# IGNITERS.net
KiCad netlist of a schematic drawn in Altium Designer
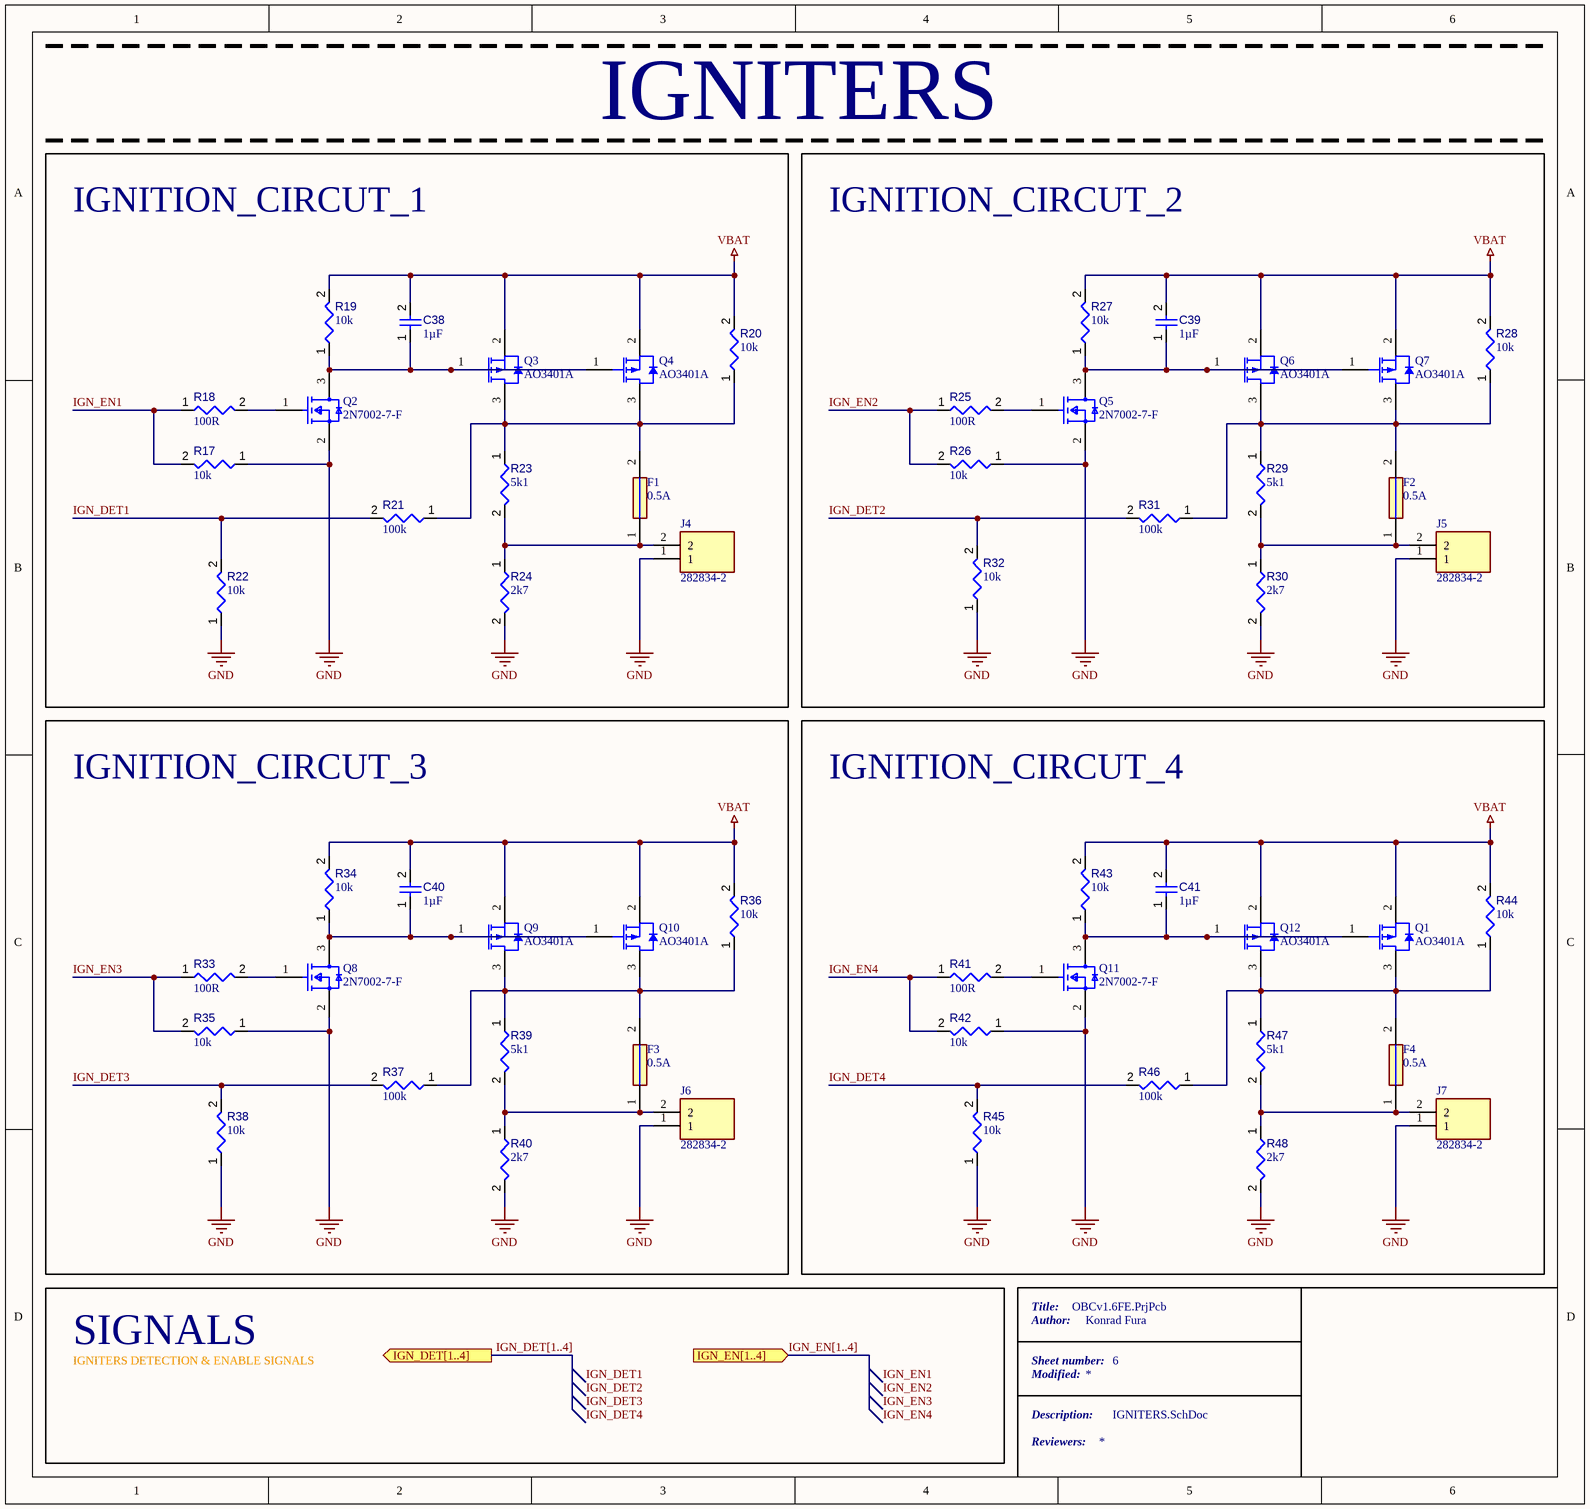
[diagram p0: IGNITERS.SchDoc]

(export (version "E")
  (design (tool "Eeschema 10.0.6"))
  (components
    (comp (ref "C38")
      (value "1µF")
      (footprint "CAPC0402(1005)60_L")
      (description "Chip Capacitor, 1µF +/-20%, 10V, 0402, Thickness 0.6 mm")
      (fields (field (name "TOLERANCE") "10%") (field (name "Comment") "Capacitor 1µF +/-20% 10V 0402"))
      (libsource (lib "PWr in Space team") (part "CAP-NP-2"))
    )
    (comp (ref "C39")
      (value "1µF")
      (footprint "CAPC0402(1005)60_L")
      (description "Chip Capacitor, 1µF +/-20%, 10V, 0402, Thickness 0.6 mm")
      (fields (field (name "TOLERANCE") "10%") (field (name "Comment") "Capacitor 1µF +/-20% 10V 0402"))
      (libsource (lib "PWr in Space team") (part "CAP-NP-2"))
    )
    (comp (ref "C40")
      (value "1µF")
      (footprint "CAPC0402(1005)60_L")
      (description "Chip Capacitor, 1µF +/-20%, 10V, 0402, Thickness 0.6 mm")
      (fields (field (name "TOLERANCE") "10%") (field (name "Comment") "Capacitor 1µF +/-20% 10V 0402"))
      (libsource (lib "PWr in Space team") (part "CAP-NP-2"))
    )
    (comp (ref "C41")
      (value "1µF")
      (footprint "CAPC0402(1005)60_L")
      (description "Chip Capacitor, 1µF +/-20%, 10V, 0402, Thickness 0.6 mm")
      (fields (field (name "TOLERANCE") "10%") (field (name "Comment") "Capacitor 1µF +/-20% 10V 0402"))
      (libsource (lib "PWr in Space team") (part "CAP-NP-2"))
    )
    (comp (ref "F1")
      (value "0.5A")
      (footprint "SamacSys:FUSC2114X75N")
      (description "Fuse")
      (fields
        (field (name "MANUFACTURER_PART_NUMBER") "0805L020/24YR")
        (field (name "MOUSER PART NUMBER") "576-0805L020/24YR")
      )
      (libsource (lib "*") (part "0805L020_24YR"))
    )
    (comp (ref "F2")
      (value "0.5A")
      (footprint "SamacSys:FUSC2114X75N")
      (description "Fuse")
      (fields
        (field (name "MANUFACTURER_PART_NUMBER") "0805L020/24YR")
        (field (name "MOUSER PART NUMBER") "576-0805L020/24YR")
      )
      (libsource (lib "*") (part "0805L020_24YR"))
    )
    (comp (ref "F3")
      (value "0.5A")
      (footprint "SamacSys:FUSC2114X75N")
      (description "Fuse")
      (fields
        (field (name "MANUFACTURER_PART_NUMBER") "0805L020/24YR")
        (field (name "MOUSER PART NUMBER") "576-0805L020/24YR")
      )
      (libsource (lib "*") (part "0805L020_24YR"))
    )
    (comp (ref "F4")
      (value "0.5A")
      (footprint "SamacSys:FUSC2114X75N")
      (description "Fuse")
      (fields
        (field (name "MANUFACTURER_PART_NUMBER") "0805L020/24YR")
        (field (name "MOUSER PART NUMBER") "576-0805L020/24YR")
      )
      (libsource (lib "*") (part "0805L020_24YR"))
    )
    (comp (ref "J4")
      (value "282834-2")
      (footprint "SamacSys:282834-2_1")
      (description "Connector")
      (fields (field (name "MOUSER PART NUMBER") "571-282834-2"))
      (libsource (lib "*") (part "282834-2"))
    )
    (comp (ref "J5")
      (value "282834-2")
      (footprint "SamacSys:282834-2_1")
      (description "Connector")
      (fields (field (name "MOUSER PART NUMBER") "571-282834-2"))
      (libsource (lib "*") (part "282834-2"))
    )
    (comp (ref "J6")
      (value "282834-2")
      (footprint "SamacSys:282834-2_1")
      (description "Connector")
      (fields (field (name "MOUSER PART NUMBER") "571-282834-2"))
      (libsource (lib "*") (part "282834-2"))
    )
    (comp (ref "J7")
      (value "282834-2")
      (footprint "SamacSys:282834-2_1")
      (description "Connector")
      (fields (field (name "MOUSER PART NUMBER") "571-282834-2"))
      (libsource (lib "*") (part "282834-2"))
    )
    (comp (ref "Q1")
      (value "AO3401A")
      (footprint "AO-SOT-23-3L_V")
      (description "P-Channel MOSFET, 30 V, 4 A, -55 to 150 degC, 3-Pin SOT-23-3L, RoHS, Tape and Reel")
      (fields (field (name "MANUFACTURER") "Alpha and Omega"))
      (libsource (lib "Altium Content Vault") (part "PEMOS-GSD-3"))
    )
    (comp (ref "Q2")
      (value "2N7002-7-F")
      (footprint "FP-SOT23-MFG")
      (description "MOSFET N-CH 60V 115MA SOT23-3")
      (fields (field (name "VOLTAGE") "60V"))
      (libsource (lib "Altium Content Vault") (part "3b9c635fedb024a5347a57b145af9cc"))
    )
    (comp (ref "Q3")
      (value "AO3401A")
      (footprint "AO-SOT-23-3L_V")
      (description "P-Channel MOSFET, 30 V, 4 A, -55 to 150 degC, 3-Pin SOT-23-3L, RoHS, Tape and Reel")
      (fields (field (name "MANUFACTURER") "Alpha and Omega"))
      (libsource (lib "Altium Content Vault") (part "PEMOS-GSD-3"))
    )
    (comp (ref "Q4")
      (value "AO3401A")
      (footprint "AO-SOT-23-3L_V")
      (description "P-Channel MOSFET, 30 V, 4 A, -55 to 150 degC, 3-Pin SOT-23-3L, RoHS, Tape and Reel")
      (fields (field (name "MANUFACTURER") "Alpha and Omega"))
      (libsource (lib "Altium Content Vault") (part "PEMOS-GSD-3"))
    )
    (comp (ref "Q5")
      (value "2N7002-7-F")
      (footprint "FP-SOT23-MFG")
      (description "MOSFET N-CH 60V 115MA SOT23-3")
      (fields (field (name "VOLTAGE") "60V"))
      (libsource (lib "Altium Content Vault") (part "3b9c635fedb024a5347a57b145af9cc"))
    )
    (comp (ref "Q6")
      (value "AO3401A")
      (footprint "AO-SOT-23-3L_V")
      (description "P-Channel MOSFET, 30 V, 4 A, -55 to 150 degC, 3-Pin SOT-23-3L, RoHS, Tape and Reel")
      (fields (field (name "MANUFACTURER") "Alpha and Omega"))
      (libsource (lib "Altium Content Vault") (part "PEMOS-GSD-3"))
    )
    (comp (ref "Q7")
      (value "AO3401A")
      (footprint "AO-SOT-23-3L_V")
      (description "P-Channel MOSFET, 30 V, 4 A, -55 to 150 degC, 3-Pin SOT-23-3L, RoHS, Tape and Reel")
      (fields (field (name "MANUFACTURER") "Alpha and Omega"))
      (libsource (lib "Altium Content Vault") (part "PEMOS-GSD-3"))
    )
    (comp (ref "Q8")
      (value "2N7002-7-F")
      (footprint "FP-SOT23-MFG")
      (description "MOSFET N-CH 60V 115MA SOT23-3")
      (fields (field (name "VOLTAGE") "60V"))
      (libsource (lib "Altium Content Vault") (part "3b9c635fedb024a5347a57b145af9cc"))
    )
    (comp (ref "Q9")
      (value "AO3401A")
      (footprint "AO-SOT-23-3L_V")
      (description "P-Channel MOSFET, 30 V, 4 A, -55 to 150 degC, 3-Pin SOT-23-3L, RoHS, Tape and Reel")
      (fields (field (name "MANUFACTURER") "Alpha and Omega"))
      (libsource (lib "Altium Content Vault") (part "PEMOS-GSD-3"))
    )
    (comp (ref "Q10")
      (value "AO3401A")
      (footprint "AO-SOT-23-3L_V")
      (description "P-Channel MOSFET, 30 V, 4 A, -55 to 150 degC, 3-Pin SOT-23-3L, RoHS, Tape and Reel")
      (fields (field (name "MANUFACTURER") "Alpha and Omega"))
      (libsource (lib "Altium Content Vault") (part "PEMOS-GSD-3"))
    )
    (comp (ref "Q11")
      (value "2N7002-7-F")
      (footprint "FP-SOT23-MFG")
      (description "MOSFET N-CH 60V 115MA SOT23-3")
      (fields (field (name "VOLTAGE") "60V"))
      (libsource (lib "Altium Content Vault") (part "3b9c635fedb024a5347a57b145af9cc"))
    )
    (comp (ref "Q12")
      (value "AO3401A")
      (footprint "AO-SOT-23-3L_V")
      (description "P-Channel MOSFET, 30 V, 4 A, -55 to 150 degC, 3-Pin SOT-23-3L, RoHS, Tape and Reel")
      (fields (field (name "MANUFACTURER") "Alpha and Omega"))
      (libsource (lib "Altium Content Vault") (part "PEMOS-GSD-3"))
    )
    (comp (ref "R17")
      (value "10k")
      (footprint "RESC0402(1005)_L")
      (description "Chip Resistor, 10 kOhms, +/-1 %, 63 mW, -55 to 125 degC, 0402")
      (fields (field (name "POWER") "63mW") (field (name "TOLERANCE") "1%"))
      (libsource (lib "PWr in Space team") (part "RES-2"))
    )
    (comp (ref "R18")
      (value "100R")
      (footprint "RESC0402(1005)_L")
      (description "Chip Resistor, 100 Ohms, +/-1 %, 63 mW, -55 to 155 degC, 0402")
      (fields (field (name "POWER") "63mW") (field (name "TOLERANCE") "1%"))
      (libsource (lib "PWr in Space team") (part "RES-2"))
    )
    (comp (ref "R19")
      (value "10k")
      (footprint "RESC0402(1005)_L")
      (description "Chip Resistor, 10 kOhms, +/-1 %, 63 mW, -55 to 125 degC, 0402")
      (fields (field (name "POWER") "63mW") (field (name "TOLERANCE") "1%"))
      (libsource (lib "PWr in Space team") (part "RES-2"))
    )
    (comp (ref "R20")
      (value "10k")
      (footprint "RESC0402(1005)_L")
      (description "Chip Resistor, 10 kOhms, +/-1 %, 63 mW, -55 to 125 degC, 0402")
      (fields (field (name "POWER") "63mW") (field (name "TOLERANCE") "1%"))
      (libsource (lib "PWr in Space team") (part "RES-2"))
    )
    (comp (ref "R21")
      (value "100k")
      (footprint "RESC0402(1005)_L")
      (description "Chip Resistor, 100 kOhms, +/-1 %, 63 mW, -55 to 155 degC, 0402")
      (fields (field (name "TOLERANCE") "1%") (field (name "POWER") "63mW"))
      (libsource (lib "PWr in Space team") (part "RES-2"))
    )
    (comp (ref "R22")
      (value "10k")
      (footprint "RESC0402(1005)_L")
      (description "Chip Resistor, 10 kOhms, +/-1 %, 63 mW, -55 to 125 degC, 0402")
      (fields (field (name "POWER") "63mW") (field (name "TOLERANCE") "1%"))
      (libsource (lib "PWr in Space team") (part "RES-2"))
    )
    (comp (ref "R23")
      (value "5k1")
      (footprint "RESC0402(1005)_L")
      (description "Chip Resistor, 5.1 kOhms, +/-1 %, 63 mW, -55 to 155 degC, 0402")
      (fields (field (name "TOLERANCE") "1%") (field (name "POWER") "63mW"))
      (libsource (lib "PWr in Space team") (part "RES-2"))
    )
    (comp (ref "R24")
      (value "2k7")
      (footprint "RESC0402(1005)_L")
      (description "Chip Resistor, 2.7 kOhms, +/-1 %, 63 mW, -55 to 155 degC, 0402")
      (fields (field (name "TOLERANCE") "1%") (field (name "POWER") "63mW"))
      (libsource (lib "PWr in Space team") (part "RES-2"))
    )
    (comp (ref "R25")
      (value "100R")
      (footprint "RESC0402(1005)_L")
      (description "Chip Resistor, 100 Ohms, +/-1 %, 63 mW, -55 to 155 degC, 0402")
      (fields (field (name "POWER") "63mW") (field (name "TOLERANCE") "1%"))
      (libsource (lib "PWr in Space team") (part "RES-2"))
    )
    (comp (ref "R26")
      (value "10k")
      (footprint "RESC0402(1005)_L")
      (description "Chip Resistor, 10 kOhms, +/-1 %, 63 mW, -55 to 125 degC, 0402")
      (fields (field (name "POWER") "63mW") (field (name "TOLERANCE") "1%"))
      (libsource (lib "PWr in Space team") (part "RES-2"))
    )
    (comp (ref "R27")
      (value "10k")
      (footprint "RESC0402(1005)_L")
      (description "Chip Resistor, 10 kOhms, +/-1 %, 63 mW, -55 to 125 degC, 0402")
      (fields (field (name "POWER") "63mW") (field (name "TOLERANCE") "1%"))
      (libsource (lib "PWr in Space team") (part "RES-2"))
    )
    (comp (ref "R28")
      (value "10k")
      (footprint "RESC0402(1005)_L")
      (description "Chip Resistor, 10 kOhms, +/-1 %, 63 mW, -55 to 125 degC, 0402")
      (fields (field (name "POWER") "63mW") (field (name "TOLERANCE") "1%"))
      (libsource (lib "PWr in Space team") (part "RES-2"))
    )
    (comp (ref "R29")
      (value "5k1")
      (footprint "RESC0402(1005)_L")
      (description "Chip Resistor, 5.1 kOhms, +/-1 %, 63 mW, -55 to 155 degC, 0402")
      (fields (field (name "TOLERANCE") "1%") (field (name "POWER") "63mW"))
      (libsource (lib "PWr in Space team") (part "RES-2"))
    )
    (comp (ref "R30")
      (value "2k7")
      (footprint "RESC0402(1005)_L")
      (description "Chip Resistor, 2.7 kOhms, +/-1 %, 63 mW, -55 to 155 degC, 0402")
      (fields (field (name "TOLERANCE") "1%") (field (name "POWER") "63mW"))
      (libsource (lib "PWr in Space team") (part "RES-2"))
    )
    (comp (ref "R31")
      (value "100k")
      (footprint "RESC0402(1005)_L")
      (description "Chip Resistor, 100 kOhms, +/-1 %, 63 mW, -55 to 155 degC, 0402")
      (fields (field (name "TOLERANCE") "1%") (field (name "POWER") "63mW"))
      (libsource (lib "PWr in Space team") (part "RES-2"))
    )
    (comp (ref "R32")
      (value "10k")
      (footprint "RESC0402(1005)_L")
      (description "Chip Resistor, 10 kOhms, +/-1 %, 63 mW, -55 to 125 degC, 0402")
      (fields (field (name "POWER") "63mW") (field (name "TOLERANCE") "1%"))
      (libsource (lib "PWr in Space team") (part "RES-2"))
    )
    (comp (ref "R33")
      (value "100R")
      (footprint "RESC0402(1005)_L")
      (description "Chip Resistor, 100 Ohms, +/-1 %, 63 mW, -55 to 155 degC, 0402")
      (fields (field (name "POWER") "63mW") (field (name "TOLERANCE") "1%"))
      (libsource (lib "PWr in Space team") (part "RES-2"))
    )
    (comp (ref "R34")
      (value "10k")
      (footprint "RESC0402(1005)_L")
      (description "Chip Resistor, 10 kOhms, +/-1 %, 63 mW, -55 to 125 degC, 0402")
      (fields (field (name "POWER") "63mW") (field (name "TOLERANCE") "1%"))
      (libsource (lib "PWr in Space team") (part "RES-2"))
    )
    (comp (ref "R35")
      (value "10k")
      (footprint "RESC0402(1005)_L")
      (description "Chip Resistor, 10 kOhms, +/-1 %, 63 mW, -55 to 125 degC, 0402")
      (fields (field (name "POWER") "63mW") (field (name "TOLERANCE") "1%"))
      (libsource (lib "PWr in Space team") (part "RES-2"))
    )
    (comp (ref "R36")
      (value "10k")
      (footprint "RESC0402(1005)_L")
      (description "Chip Resistor, 10 kOhms, +/-1 %, 63 mW, -55 to 125 degC, 0402")
      (fields (field (name "POWER") "63mW") (field (name "TOLERANCE") "1%"))
      (libsource (lib "PWr in Space team") (part "RES-2"))
    )
    (comp (ref "R37")
      (value "100k")
      (footprint "RESC0402(1005)_L")
      (description "Chip Resistor, 100 kOhms, +/-1 %, 63 mW, -55 to 155 degC, 0402")
      (fields (field (name "TOLERANCE") "1%") (field (name "POWER") "63mW"))
      (libsource (lib "PWr in Space team") (part "RES-2"))
    )
    (comp (ref "R38")
      (value "10k")
      (footprint "RESC0402(1005)_L")
      (description "Chip Resistor, 10 kOhms, +/-1 %, 63 mW, -55 to 125 degC, 0402")
      (fields (field (name "POWER") "63mW") (field (name "TOLERANCE") "1%"))
      (libsource (lib "PWr in Space team") (part "RES-2"))
    )
    (comp (ref "R39")
      (value "5k1")
      (footprint "RESC0402(1005)_L")
      (description "Chip Resistor, 5.1 kOhms, +/-1 %, 63 mW, -55 to 155 degC, 0402")
      (fields (field (name "TOLERANCE") "1%") (field (name "POWER") "63mW"))
      (libsource (lib "PWr in Space team") (part "RES-2"))
    )
    (comp (ref "R40")
      (value "2k7")
      (footprint "RESC0402(1005)_L")
      (description "Chip Resistor, 2.7 kOhms, +/-1 %, 63 mW, -55 to 155 degC, 0402")
      (fields (field (name "TOLERANCE") "1%") (field (name "POWER") "63mW"))
      (libsource (lib "PWr in Space team") (part "RES-2"))
    )
    (comp (ref "R41")
      (value "100R")
      (footprint "RESC0402(1005)_L")
      (description "Chip Resistor, 100 Ohms, +/-1 %, 63 mW, -55 to 155 degC, 0402")
      (fields (field (name "POWER") "63mW") (field (name "TOLERANCE") "1%"))
      (libsource (lib "PWr in Space team") (part "RES-2"))
    )
    (comp (ref "R42")
      (value "10k")
      (footprint "RESC0402(1005)_L")
      (description "Chip Resistor, 10 kOhms, +/-1 %, 63 mW, -55 to 125 degC, 0402")
      (fields (field (name "POWER") "63mW") (field (name "TOLERANCE") "1%"))
      (libsource (lib "PWr in Space team") (part "RES-2"))
    )
    (comp (ref "R43")
      (value "10k")
      (footprint "RESC0402(1005)_L")
      (description "Chip Resistor, 10 kOhms, +/-1 %, 63 mW, -55 to 125 degC, 0402")
      (fields (field (name "POWER") "63mW") (field (name "TOLERANCE") "1%"))
      (libsource (lib "PWr in Space team") (part "RES-2"))
    )
    (comp (ref "R44")
      (value "10k")
      (footprint "RESC0402(1005)_L")
      (description "Chip Resistor, 10 kOhms, +/-1 %, 63 mW, -55 to 125 degC, 0402")
      (fields (field (name "POWER") "63mW") (field (name "TOLERANCE") "1%"))
      (libsource (lib "PWr in Space team") (part "RES-2"))
    )
    (comp (ref "R45")
      (value "10k")
      (footprint "RESC0402(1005)_L")
      (description "Chip Resistor, 10 kOhms, +/-1 %, 63 mW, -55 to 125 degC, 0402")
      (fields (field (name "POWER") "63mW") (field (name "TOLERANCE") "1%"))
      (libsource (lib "PWr in Space team") (part "RES-2"))
    )
    (comp (ref "R46")
      (value "100k")
      (footprint "RESC0402(1005)_L")
      (description "Chip Resistor, 100 kOhms, +/-1 %, 63 mW, -55 to 155 degC, 0402")
      (fields (field (name "TOLERANCE") "1%") (field (name "POWER") "63mW"))
      (libsource (lib "PWr in Space team") (part "RES-2"))
    )
    (comp (ref "R47")
      (value "5k1")
      (footprint "RESC0402(1005)_L")
      (description "Chip Resistor, 5.1 kOhms, +/-1 %, 63 mW, -55 to 155 degC, 0402")
      (fields (field (name "TOLERANCE") "1%") (field (name "POWER") "63mW"))
      (libsource (lib "PWr in Space team") (part "RES-2"))
    )
    (comp (ref "R48")
      (value "2k7")
      (footprint "RESC0402(1005)_L")
      (description "Chip Resistor, 2.7 kOhms, +/-1 %, 63 mW, -55 to 155 degC, 0402")
      (fields (field (name "TOLERANCE") "1%") (field (name "POWER") "63mW"))
      (libsource (lib "PWr in Space team") (part "RES-2"))
    )
  )
  (nets
    (net (code "1") (name "/IGN_DET1") (class "Default")
      (node (ref "R21") (pin "2") (pinfunction "2_2") (pintype "passive"))
      (node (ref "R22") (pin "2") (pinfunction "2_2") (pintype "passive"))
    )
    (net (code "2") (name "/IGN_DET2") (class "Default")
      (node (ref "R31") (pin "2") (pinfunction "2_2") (pintype "passive"))
      (node (ref "R32") (pin "2") (pinfunction "2_2") (pintype "passive"))
    )
    (net (code "3") (name "/IGN_DET3") (class "Default")
      (node (ref "R37") (pin "2") (pinfunction "2_2") (pintype "passive"))
      (node (ref "R38") (pin "2") (pinfunction "2_2") (pintype "passive"))
    )
    (net (code "4") (name "/IGN_DET4") (class "Default")
      (node (ref "R45") (pin "2") (pinfunction "2_2") (pintype "passive"))
      (node (ref "R46") (pin "2") (pinfunction "2_2") (pintype "passive"))
    )
    (net (code "6") (name "/IGN_EN1") (class "Default")
      (node (ref "R17") (pin "2") (pinfunction "2_2") (pintype "passive"))
      (node (ref "R18") (pin "1") (pinfunction "1_1") (pintype "passive"))
    )
    (net (code "7") (name "/IGN_EN2") (class "Default")
      (node (ref "R25") (pin "1") (pinfunction "1_1") (pintype "passive"))
      (node (ref "R26") (pin "2") (pinfunction "2_2") (pintype "passive"))
    )
    (net (code "8") (name "/IGN_EN3") (class "Default")
      (node (ref "R33") (pin "1") (pinfunction "1_1") (pintype "passive"))
      (node (ref "R35") (pin "2") (pinfunction "2_2") (pintype "passive"))
    )
    (net (code "9") (name "/IGN_EN4") (class "Default")
      (node (ref "R41") (pin "1") (pinfunction "1_1") (pintype "passive"))
      (node (ref "R42") (pin "2") (pinfunction "2_2") (pintype "passive"))
    )
    (net (code "11") (name "GND") (class "Default")
      (node (ref "J4") (pin "1") (pinfunction "1_1") (pintype "passive"))
      (node (ref "J5") (pin "1") (pinfunction "1_1") (pintype "passive"))
      (node (ref "J6") (pin "1") (pinfunction "1_1") (pintype "passive"))
      (node (ref "J7") (pin "1") (pinfunction "1_1") (pintype "passive"))
      (node (ref "Q11") (pin "2") (pinfunction "S_2") (pintype "passive"))
      (node (ref "Q2") (pin "2") (pinfunction "S_2") (pintype "passive"))
      (node (ref "Q5") (pin "2") (pinfunction "S_2") (pintype "passive"))
      (node (ref "Q8") (pin "2") (pinfunction "S_2") (pintype "passive"))
      (node (ref "R17") (pin "1") (pinfunction "1_1") (pintype "passive"))
      (node (ref "R22") (pin "1") (pinfunction "1_1") (pintype "passive"))
      (node (ref "R24") (pin "2") (pinfunction "2_2") (pintype "passive"))
      (node (ref "R26") (pin "1") (pinfunction "1_1") (pintype "passive"))
      (node (ref "R30") (pin "2") (pinfunction "2_2") (pintype "passive"))
      (node (ref "R32") (pin "1") (pinfunction "1_1") (pintype "passive"))
      (node (ref "R35") (pin "1") (pinfunction "1_1") (pintype "passive"))
      (node (ref "R38") (pin "1") (pinfunction "1_1") (pintype "passive"))
      (node (ref "R40") (pin "2") (pinfunction "2_2") (pintype "passive"))
      (node (ref "R42") (pin "1") (pinfunction "1_1") (pintype "passive"))
      (node (ref "R45") (pin "1") (pinfunction "1_1") (pintype "passive"))
      (node (ref "R48") (pin "2") (pinfunction "2_2") (pintype "passive"))
    )
    (net (code "12") (name "Net-(F1-Pad1)") (class "Default")
      (node (ref "F1") (pin "1") (pinfunction "1_1") (pintype "passive"))
      (node (ref "J4") (pin "2") (pinfunction "2_2") (pintype "passive"))
      (node (ref "R23") (pin "2") (pinfunction "2_2") (pintype "passive"))
      (node (ref "R24") (pin "1") (pinfunction "1_1") (pintype "passive"))
    )
    (net (code "13") (name "Net-(F2-Pad1)") (class "Default")
      (node (ref "F2") (pin "1") (pinfunction "1_1") (pintype "passive"))
      (node (ref "J5") (pin "2") (pinfunction "2_2") (pintype "passive"))
      (node (ref "R29") (pin "2") (pinfunction "2_2") (pintype "passive"))
      (node (ref "R30") (pin "1") (pinfunction "1_1") (pintype "passive"))
    )
    (net (code "14") (name "Net-(F3-Pad1)") (class "Default")
      (node (ref "F3") (pin "1") (pinfunction "1_1") (pintype "passive"))
      (node (ref "J6") (pin "2") (pinfunction "2_2") (pintype "passive"))
      (node (ref "R39") (pin "2") (pinfunction "2_2") (pintype "passive"))
      (node (ref "R40") (pin "1") (pinfunction "1_1") (pintype "passive"))
    )
    (net (code "15") (name "Net-(F4-Pad1)") (class "Default")
      (node (ref "F4") (pin "1") (pinfunction "1_1") (pintype "passive"))
      (node (ref "J7") (pin "2") (pinfunction "2_2") (pintype "passive"))
      (node (ref "R47") (pin "2") (pinfunction "2_2") (pintype "passive"))
      (node (ref "R48") (pin "1") (pinfunction "1_1") (pintype "passive"))
    )
    (net (code "16") (name "Net-(Q1-DRAIN)") (class "Default")
      (node (ref "F4") (pin "2") (pinfunction "2_2") (pintype "passive"))
      (node (ref "Q1") (pin "3") (pinfunction "DRAIN_3") (pintype "passive"))
      (node (ref "Q12") (pin "3") (pinfunction "DRAIN_3") (pintype "passive"))
      (node (ref "R44") (pin "1") (pinfunction "1_1") (pintype "passive"))
      (node (ref "R46") (pin "1") (pinfunction "1_1") (pintype "passive"))
      (node (ref "R47") (pin "1") (pinfunction "1_1") (pintype "passive"))
    )
    (net (code "17") (name "Net-(Q1-GATE)") (class "Default")
      (node (ref "C41") (pin "1") (pinfunction "1_1") (pintype "passive"))
      (node (ref "Q1") (pin "1") (pinfunction "GATE_1") (pintype "passive"))
      (node (ref "Q11") (pin "3") (pinfunction "D_3") (pintype "passive"))
      (node (ref "Q12") (pin "1") (pinfunction "GATE_1") (pintype "passive"))
      (node (ref "R43") (pin "1") (pinfunction "1_1") (pintype "passive"))
    )
    (net (code "18") (name "Net-(Q2-D)") (class "Default")
      (node (ref "C38") (pin "1") (pinfunction "1_1") (pintype "passive"))
      (node (ref "Q2") (pin "3") (pinfunction "D_3") (pintype "passive"))
      (node (ref "Q3") (pin "1") (pinfunction "GATE_1") (pintype "passive"))
      (node (ref "Q4") (pin "1") (pinfunction "GATE_1") (pintype "passive"))
      (node (ref "R19") (pin "1") (pinfunction "1_1") (pintype "passive"))
    )
    (net (code "19") (name "Net-(Q2-G)") (class "Default")
      (node (ref "Q2") (pin "1") (pinfunction "G_1") (pintype "passive"))
      (node (ref "R18") (pin "2") (pinfunction "2_2") (pintype "passive"))
    )
    (net (code "20") (name "Net-(Q3-DRAIN)") (class "Default")
      (node (ref "F1") (pin "2") (pinfunction "2_2") (pintype "passive"))
      (node (ref "Q3") (pin "3") (pinfunction "DRAIN_3") (pintype "passive"))
      (node (ref "Q4") (pin "3") (pinfunction "DRAIN_3") (pintype "passive"))
      (node (ref "R20") (pin "1") (pinfunction "1_1") (pintype "passive"))
      (node (ref "R21") (pin "1") (pinfunction "1_1") (pintype "passive"))
      (node (ref "R23") (pin "1") (pinfunction "1_1") (pintype "passive"))
    )
    (net (code "21") (name "Net-(Q5-D)") (class "Default")
      (node (ref "C39") (pin "1") (pinfunction "1_1") (pintype "passive"))
      (node (ref "Q5") (pin "3") (pinfunction "D_3") (pintype "passive"))
      (node (ref "Q6") (pin "1") (pinfunction "GATE_1") (pintype "passive"))
      (node (ref "Q7") (pin "1") (pinfunction "GATE_1") (pintype "passive"))
      (node (ref "R27") (pin "1") (pinfunction "1_1") (pintype "passive"))
    )
    (net (code "22") (name "Net-(Q5-G)") (class "Default")
      (node (ref "Q5") (pin "1") (pinfunction "G_1") (pintype "passive"))
      (node (ref "R25") (pin "2") (pinfunction "2_2") (pintype "passive"))
    )
    (net (code "23") (name "Net-(Q6-DRAIN)") (class "Default")
      (node (ref "F2") (pin "2") (pinfunction "2_2") (pintype "passive"))
      (node (ref "Q6") (pin "3") (pinfunction "DRAIN_3") (pintype "passive"))
      (node (ref "Q7") (pin "3") (pinfunction "DRAIN_3") (pintype "passive"))
      (node (ref "R28") (pin "1") (pinfunction "1_1") (pintype "passive"))
      (node (ref "R29") (pin "1") (pinfunction "1_1") (pintype "passive"))
      (node (ref "R31") (pin "1") (pinfunction "1_1") (pintype "passive"))
    )
    (net (code "24") (name "Net-(Q8-G)") (class "Default")
      (node (ref "Q8") (pin "1") (pinfunction "G_1") (pintype "passive"))
      (node (ref "R33") (pin "2") (pinfunction "2_2") (pintype "passive"))
    )
    (net (code "25") (name "Net-(Q10-DRAIN)") (class "Default")
      (node (ref "F3") (pin "2") (pinfunction "2_2") (pintype "passive"))
      (node (ref "Q10") (pin "3") (pinfunction "DRAIN_3") (pintype "passive"))
      (node (ref "Q9") (pin "3") (pinfunction "DRAIN_3") (pintype "passive"))
      (node (ref "R36") (pin "1") (pinfunction "1_1") (pintype "passive"))
      (node (ref "R37") (pin "1") (pinfunction "1_1") (pintype "passive"))
      (node (ref "R39") (pin "1") (pinfunction "1_1") (pintype "passive"))
    )
    (net (code "26") (name "Net-(Q10-GATE)") (class "Default")
      (node (ref "C40") (pin "1") (pinfunction "1_1") (pintype "passive"))
      (node (ref "Q10") (pin "1") (pinfunction "GATE_1") (pintype "passive"))
      (node (ref "Q8") (pin "3") (pinfunction "D_3") (pintype "passive"))
      (node (ref "Q9") (pin "1") (pinfunction "GATE_1") (pintype "passive"))
      (node (ref "R34") (pin "1") (pinfunction "1_1") (pintype "passive"))
    )
    (net (code "27") (name "Net-(Q11-G)") (class "Default")
      (node (ref "Q11") (pin "1") (pinfunction "G_1") (pintype "passive"))
      (node (ref "R41") (pin "2") (pinfunction "2_2") (pintype "passive"))
    )
    (net (code "28") (name "VBAT") (class "Default")
      (node (ref "C38") (pin "2") (pinfunction "2_2") (pintype "passive"))
      (node (ref "C39") (pin "2") (pinfunction "2_2") (pintype "passive"))
      (node (ref "C40") (pin "2") (pinfunction "2_2") (pintype "passive"))
      (node (ref "C41") (pin "2") (pinfunction "2_2") (pintype "passive"))
      (node (ref "Q1") (pin "2") (pinfunction "SOURCE_2") (pintype "passive"))
      (node (ref "Q10") (pin "2") (pinfunction "SOURCE_2") (pintype "passive"))
      (node (ref "Q12") (pin "2") (pinfunction "SOURCE_2") (pintype "passive"))
      (node (ref "Q3") (pin "2") (pinfunction "SOURCE_2") (pintype "passive"))
      (node (ref "Q4") (pin "2") (pinfunction "SOURCE_2") (pintype "passive"))
      (node (ref "Q6") (pin "2") (pinfunction "SOURCE_2") (pintype "passive"))
      (node (ref "Q7") (pin "2") (pinfunction "SOURCE_2") (pintype "passive"))
      (node (ref "Q9") (pin "2") (pinfunction "SOURCE_2") (pintype "passive"))
      (node (ref "R19") (pin "2") (pinfunction "2_2") (pintype "passive"))
      (node (ref "R20") (pin "2") (pinfunction "2_2") (pintype "passive"))
      (node (ref "R27") (pin "2") (pinfunction "2_2") (pintype "passive"))
      (node (ref "R28") (pin "2") (pinfunction "2_2") (pintype "passive"))
      (node (ref "R34") (pin "2") (pinfunction "2_2") (pintype "passive"))
      (node (ref "R36") (pin "2") (pinfunction "2_2") (pintype "passive"))
      (node (ref "R43") (pin "2") (pinfunction "2_2") (pintype "passive"))
      (node (ref "R44") (pin "2") (pinfunction "2_2") (pintype "passive"))
    )
  )
)
